# NFC.net
KiCad netlist of a schematic drawn in Altium Designer
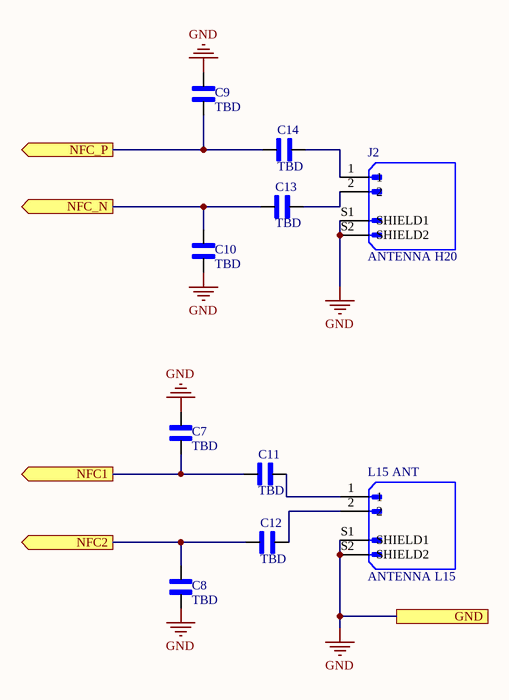
[diagram p0: NFC.SchDoc]

(export (version "E")
  (design (tool "Eeschema 10.0.6"))
  (components
    (comp (ref "C7")
      (value "TBD")
      (footprint "CAPC2012X88N")
      (description "0805 C0G/NP0 ceramic capacitor for nfc fix")
      (fields (field (name "MF") "KEMET") (field (name "MP") "C0805C473K1RACTU"))
      (libsource (lib "") (part "C0805C473K1RACTU_1"))
    )
    (comp (ref "C8")
      (value "TBD")
      (footprint "CAPC2012X88N")
      (description "0805 C0G/NP0 ceramic capacitor for nfc fix")
      (fields (field (name "MF") "KEMET") (field (name "MP") "C0805C473K1RACTU"))
      (libsource (lib "") (part "C0805C473K1RACTU_1"))
    )
    (comp (ref "C9")
      (value "TBD")
      (footprint "CAPC2012X88N")
      (description "0805 C0G/NP0 ceramic capacitor for nfc fix")
      (fields (field (name "MF") "KEMET") (field (name "MP") "C0805C473K1RACTU"))
      (libsource (lib "") (part "C0805C473K1RACTU_1"))
    )
    (comp (ref "C10")
      (value "TBD")
      (footprint "CAPC2012X88N")
      (description "0805 C0G/NP0 ceramic capacitor for nfc fix")
      (fields (field (name "MF") "KEMET") (field (name "MP") "C0805C473K1RACTU"))
      (libsource (lib "") (part "C0805C473K1RACTU_1"))
    )
    (comp (ref "C11")
      (value "TBD")
      (footprint "CAPC2012X88N")
      (description "0805 C0G/NP0 ceramic capacitor for nfc fix")
      (fields (field (name "MF") "KEMET") (field (name "MP") "C0805C473K1RACTU"))
      (libsource (lib "C0805C473K1RACTU") (part "C0805C473K1RACTU"))
    )
    (comp (ref "C12")
      (value "TBD")
      (footprint "CAPC2012X88N")
      (description "0805 C0G/NP0 ceramic capacitor for nfc fix")
      (fields (field (name "MF") "KEMET") (field (name "MP") "C0805C473K1RACTU"))
      (libsource (lib "C0805C473K1RACTU") (part "C0805C473K1RACTU"))
    )
    (comp (ref "C13")
      (value "TBD")
      (footprint "CAPC2012X88N")
      (description "0805 C0G/NP0 ceramic capacitor for nfc fix")
      (fields (field (name "MF") "KEMET") (field (name "MP") "C0805C473K1RACTU"))
      (libsource (lib "C0805C473K1RACTU") (part "C0805C473K1RACTU"))
    )
    (comp (ref "C14")
      (value "TBD")
      (footprint "CAPC2012X88N")
      (description "0805 C0G/NP0 ceramic capacitor for nfc fix")
      (fields (field (name "MF") "KEMET") (field (name "MP") "C0805C473K1RACTU"))
      (libsource (lib "C0805C473K1RACTU") (part "C0805C473K1RACTU"))
    )
    (comp (ref "J2")
      (value "ANTENNA H20")
      (footprint "MOLEX_532610271")
      (description "Connector Header Surface Mount, Right Angle 2 position 0.049 (1.25mm)")
      (fields (field (name "MP") "532610271") (field (name "MF") "Molex"))
      (libsource (lib "532610271") (part "532610271"))
    )
    (comp (ref "L15 ANT")
      (value "ANTENNA L15")
      (footprint "MOLEX_532610271")
      (description "Connector Header Surface Mount, Right Angle 2 position 0.049 (1.25mm)")
      (fields (field (name "MP") "532610271") (field (name "MF") "Molex"))
      (libsource (lib "532610271") (part "532610271"))
    )
  )
  (nets
    (net (code "1") (name "/NFC1") (class "Default")
      (node (ref "C11") (pin "2") (pinfunction "2_2") (pintype "passive"))
      (node (ref "C7") (pin "2") (pinfunction "2_2") (pintype "passive"))
    )
    (net (code "2") (name "/NFC2") (class "Default")
      (node (ref "C12") (pin "2") (pinfunction "2_2") (pintype "passive"))
      (node (ref "C8") (pin "1") (pinfunction "1_1") (pintype "passive"))
    )
    (net (code "3") (name "/NFC_N") (class "Default")
      (node (ref "C10") (pin "1") (pinfunction "1_1") (pintype "passive"))
      (node (ref "C13") (pin "2") (pinfunction "2_2") (pintype "passive"))
    )
    (net (code "4") (name "/NFC_P") (class "Default")
      (node (ref "C14") (pin "2") (pinfunction "2_2") (pintype "passive"))
      (node (ref "C9") (pin "2") (pinfunction "2_2") (pintype "passive"))
    )
    (net (code "5") (name "GND") (class "Default")
      (node (ref "C10") (pin "2") (pinfunction "2_2") (pintype "passive"))
      (node (ref "C7") (pin "1") (pinfunction "1_1") (pintype "passive"))
      (node (ref "C8") (pin "2") (pinfunction "2_2") (pintype "passive"))
      (node (ref "C9") (pin "1") (pinfunction "1_1") (pintype "passive"))
      (node (ref "J2") (pin "S1") (pinfunction "SHIELD1_S1") (pintype "passive"))
      (node (ref "J2") (pin "S2") (pinfunction "SHIELD2_S2") (pintype "passive"))
      (node (ref "L15 ANT") (pin "S1") (pinfunction "SHIELD1_S1") (pintype "passive"))
      (node (ref "L15 ANT") (pin "S2") (pinfunction "SHIELD2_S2") (pintype "passive"))
    )
    (net (code "6") (name "Net-(C11-Pad1)") (class "Default")
      (node (ref "C11") (pin "1") (pinfunction "1_1") (pintype "passive"))
      (node (ref "L15 ANT") (pin "1") (pinfunction "1_1") (pintype "passive"))
    )
    (net (code "7") (name "Net-(C12-Pad1)") (class "Default")
      (node (ref "C12") (pin "1") (pinfunction "1_1") (pintype "passive"))
      (node (ref "L15 ANT") (pin "2") (pinfunction "2_2") (pintype "passive"))
    )
    (net (code "8") (name "Net-(C13-Pad1)") (class "Default")
      (node (ref "C13") (pin "1") (pinfunction "1_1") (pintype "passive"))
      (node (ref "J2") (pin "2") (pinfunction "2_2") (pintype "passive"))
    )
    (net (code "9") (name "Net-(C14-Pad1)") (class "Default")
      (node (ref "C14") (pin "1") (pinfunction "1_1") (pintype "passive"))
      (node (ref "J2") (pin "1") (pinfunction "1_1") (pintype "passive"))
    )
  )
)
